# microcontrolador.net
KiCad netlist of a schematic drawn in Altium Designer
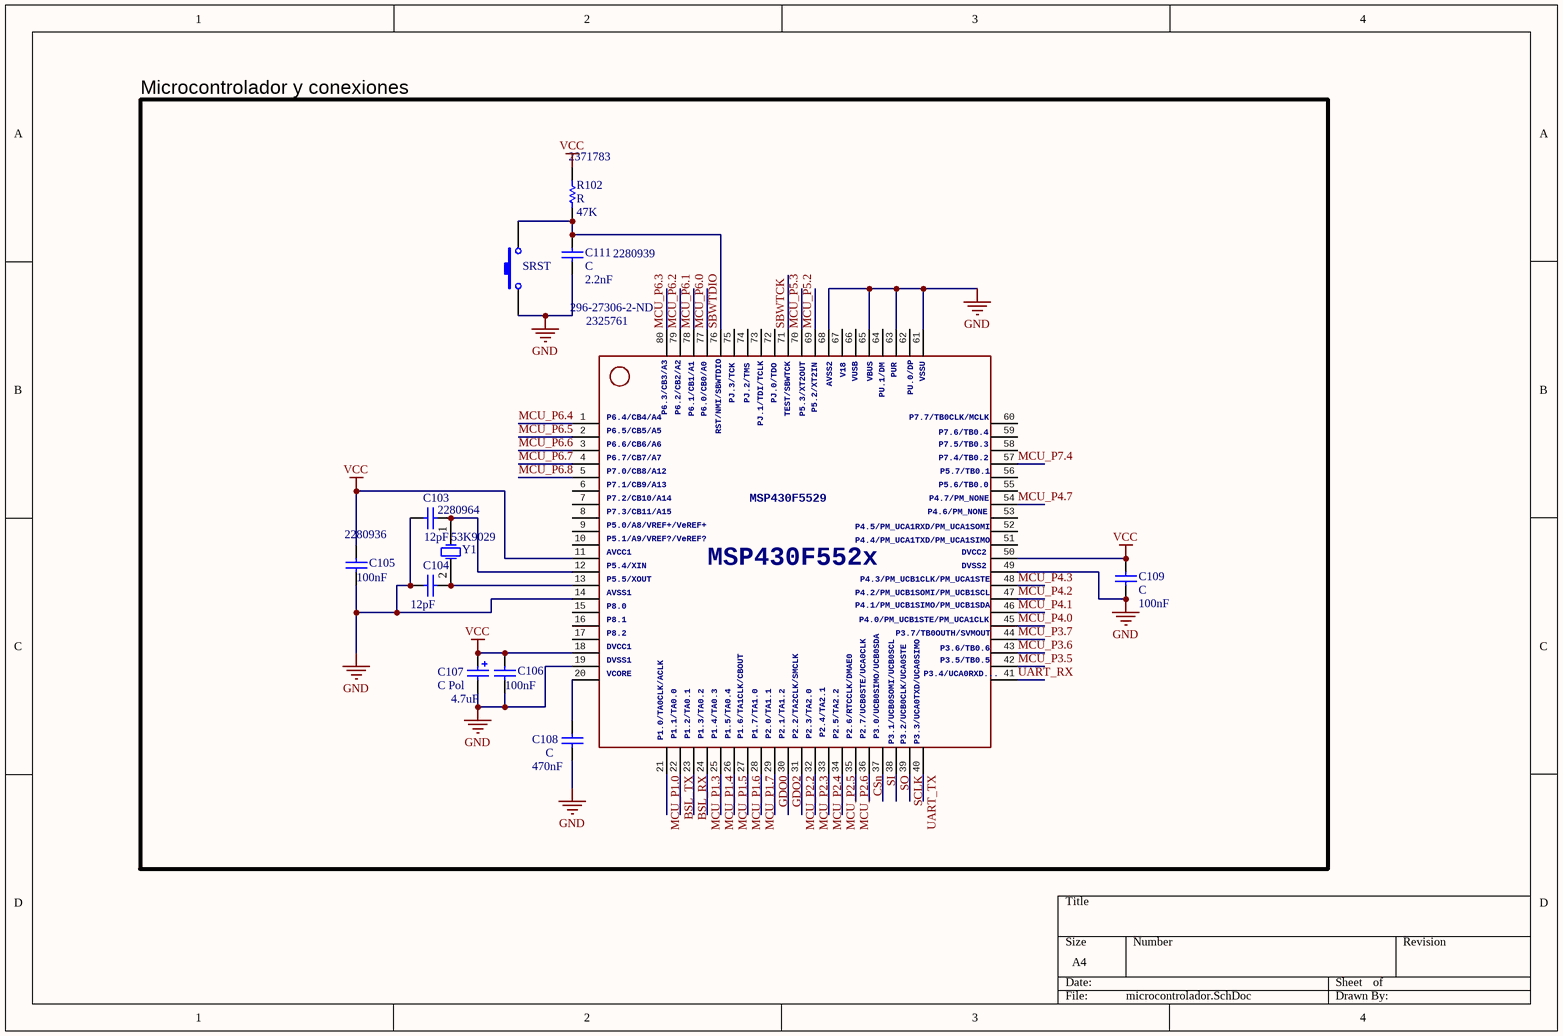
[diagram p0: microcontrolador.SchDoc]

(export (version "E")
  (design (tool "Eeschema 10.0.6"))
  (components
    (comp (ref "C103")
      (value "12pF")
      (footprint "0805 CAP")
      (description "Capacitor")
      (fields
        (field (name "MANUFACTURER") "Generic Components")
        (field (name "SUPPLIER PART NUMBER 1") "2280964")
        (field (name "Comment") "C")
        (field (name "PUBLISHER") "Altium Hobart Technology Centre")
      )
      (libsource (lib "LSI") (part "C"))
    )
    (comp (ref "C104")
      (value "12pF")
      (footprint "0805 CAP")
      (description "Capacitor")
      (fields
        (field (name "MANUFACTURER") "Generic Components")
        (field (name "Comment") "C")
        (field (name "PUBLISHER") "Altium Hobart Technology Centre")
      )
      (libsource (lib "LSI") (part "C"))
    )
    (comp (ref "C105")
      (value "100nF")
      (footprint "0805 CAP")
      (description "Capacitor")
      (fields
        (field (name "MANUFACTURER") "Generic Components")
        (field (name "SUPPLIER PART NUMBER 2") "2280936")
        (field (name "Comment") "C")
        (field (name "PUBLISHER") "Altium Hobart Technology Centre")
      )
      (libsource (lib "LSI") (part "C"))
    )
    (comp (ref "C106")
      (value "100nF")
      (footprint "0805 CAP")
      (description "Capacitor")
      (fields
        (field (name "MANUFACTURER") "Generic Components")
        (field (name "Comment") "C")
        (field (name "PUBLISHER") "Altium Hobart Technology Centre")
      )
      (libsource (lib "LSI") (part "C"))
    )
    (comp (ref "C107")
      (value "C Pol")
      (footprint "0805")
      (description "Polarized Capacitor (Surface Mount)")
      (fields
        (field (name "MANUFACTURER") "Generic Components")
        (field (name "ALTIUM_VALUE") "4.7uF")
        (field (name "PUBLISHER") "Altium Hobart Technology Centre")
      )
      (libsource (lib "LSI") (part "C Pol"))
    )
    (comp (ref "C108")
      (value "C")
      (footprint "0805 CAP")
      (description "Capacitor")
      (fields
        (field (name "MANUFACTURER") "Generic Components")
        (field (name "ALTIUM_VALUE") "470nF")
        (field (name "PUBLISHER") "Altium Hobart Technology Centre")
      )
      (libsource (lib "LSI") (part "C"))
    )
    (comp (ref "C109")
      (value "C")
      (footprint "0805 CAP")
      (description "Capacitor")
      (fields
        (field (name "MANUFACTURER") "Generic Components")
        (field (name "ALTIUM_VALUE") "100nF")
        (field (name "PUBLISHER") "Altium Hobart Technology Centre")
      )
      (libsource (lib "LSI") (part "C"))
    )
    (comp (ref "C111")
      (value "C")
      (footprint "0805 CAP")
      (description "Capacitor")
      (fields
        (field (name "MANUFACTURER") "Generic Components")
        (field (name "ALTIUM_VALUE") "2.2nF")
        (field (name "SUPPLIER PART NUMBER 1") "2280939")
        (field (name "PUBLISHER") "Altium Hobart Technology Centre")
      )
      (libsource (lib "LSI") (part "C"))
    )
    (comp (ref "MSP430F5529")
      (value "MSP430F5529IPNR")
      (footprint "TI-PN80_N")
      (fields
        (field (name "P6.3/CB3/A3") "P6.3/CB3/A3")
        (field (name "P6.2/CB2/A2") "P6.2/CB2/A2")
        (field (name "P6.1/CB1/A1") "P6.1/CB1/A1")
        (field (name "P6.0/CB0/A0") "P6.0/CB0/A0")
        (field (name "PJ.3/TCK") "PJ.3/TCK")
        (field (name "PJ.2/TMS") "PJ.2/TMS")
        (field (name "PJ.1/TDI/TCLK") "PJ.1/TDI/TCLK")
        (field (name "PJ.0/TDO") "PJ.0/TDO")
        (field (name "TEST/SBWTCK") "TEST/SBWTCK")
        (field (name "P5.3/XT2OUT") "P5.3/XT2OUT")
        (field (name "P5.2/XT2IN") "P5.2/XT2IN")
        (field (name "AVSS2") "AVSS2")
        (field (name "V18") "V18")
        (field (name "VUSB") "VUSB")
        (field (name "VBUS") "VBUS")
        (field (name "PU.1/DM") "PU.1/DM")
        (field (name "PUR") "PUR")
        (field (name "PU.0/DP") "PU.0/DP")
        (field (name "VSSU") "VSSU")
        (field (name "RST/NMI/SBWTDIO") "RST/NMI/SBWTDIO")
        (field (name "P7.7/TB0CLK/MCLK") "P7.7/TB0CLK/MCLK")
        (field (name "P7.6/TB0.4") "P7.6/TB0.4")
        (field (name "P7.5/TB0.3") "P7.5/TB0.3")
        (field (name "P7.4/TB0.2") "P7.4/TB0.2")
        (field (name "P5.7/TB0.1") "P5.7/TB0.1")
        (field (name "P5.6/TB0.0") "P5.6/TB0.0")
        (field (name "P4.7/PM_NONE") "P4.7/PM_NONE")
        (field (name "P4.5/PM_UCA1RXD/PM_UCA1SOMI") "P4.5/PM_UCA1RXD/PM_UCA1SOMI")
        (field (name "P4.4/PM_UCA1TXD/PM_UCA1SIMO") "P4.4/PM_UCA1TXD/PM_UCA1SIMO")
        (field (name "DVCC2") "DVCC2")
        (field (name "P4.3/PM_UCB1CLK/PM_UCA1STE") "P4.3/PM_UCB1CLK/PM_UCA1STE")
        (field (name "P4.2/PM_UCB1SOMI/PM_UCB1SCL") "P4.2/PM_UCB1SOMI/PM_UCB1SCL")
        (field (name "P4.1/PM_UCB1SIMO/PM_UCB1SDA") "P4.1/PM_UCB1SIMO/PM_UCB1SDA")
        (field (name "P4.0/PM_UCB1STE/PM_UCA1CLK") "P4.0/PM_UCB1STE/PM_UCA1CLK")
        (field (name "P3.7/TB0OUTH/SVMOUT") "P3.7/TB0OUTH/SVMOUT")
        (field (name "P3.6/TB0.6") "P3.6/TB0.6")
        (field (name "P4.6/PM_NONE") "P4.6/PM_NONE")
        (field (name "P3.5/TB0.5") "P3.5/TB0.5")
        (field (name "P3.4/UCA...") "P3.4/UCA0RXD...")
        (field (name "P1.0/TA0CLK/ACLK") "P1.0/TA0CLK/ACLK")
        (field (name "P1.1/TA0.0") "P1.1/TA0.0")
        (field (name "P1.2/TA0.1") "P1.2/TA0.1")
        (field (name "P1.3/TA0.2") "P1.3/TA0.2")
        (field (name "P1.4/TA0.3") "P1.4/TA0.3")
        (field (name "P1.5/TA0.4") "P1.5/TA0.4")
        (field (name "P1.6/TA1CLK/CBOUT") "P1.6/TA1CLK/CBOUT")
        (field (name "P1.7/TA1.0") "P1.7/TA1.0")
        (field (name "P2.0/TA1.1") "P2.0/TA1.1")
        (field (name "P2.1/TA1.2") "P2.1/TA1.2")
        (field (name "P2.2/TA2CLK/SMCLK") "P2.2/TA2CLK/SMCLK")
        (field (name "P2.4/TA2.1") "P2.4/TA2.1")
        (field (name "P2.5/TA2.2") "P2.5/TA2.2")
        (field (name "P2.6/RTCCLK/DMAE0") "P2.6/RTCCLK/DMAE0")
        (field (name "P2.7/UCB0STE/UCA0CLK") "P2.7/UCB0STE/UCA0CLK")
        (field (name "P3.0/UCB0SIMO/UCB0SDA") "P3.0/UCB0SIMO/UCB0SDA")
        (field (name "P3.1/UCB0SOMI/UCB0SCL") "P3.1/UCB0SOMI/UCB0SCL")
        (field (name "P3.2/UCB0CLK/UCA0STE") "P3.2/UCB0CLK/UCA0STE")
        (field (name "P3.3/UCA0TXD/UCA0SIMO") "P3.3/UCA0TXD/UCA0SIMO")
        (field (name "P6.4/CB4/A4") "P6.4/CB4/A4")
        (field (name "P6.5/CB5/A5") "P6.5/CB5/A5")
        (field (name "P6.6/CB6/A6") "P6.6/CB6/A6")
        (field (name "P6.7/CB7/A7") "P6.7/CB7/A7")
        (field (name "P7.0/CB8/A12") "P7.0/CB8/A12")
        (field (name "P7.1/CB9/A13") "P7.1/CB9/A13")
        (field (name "P7.2/CB10/A14") "P7.2/CB10/A14")
        (field (name "P7.3/CB11/A15") "P7.3/CB11/A15")
        (field (name "P5.0/A8/VREF+/VEREF+") "P5.0/A8/VREF+/VeREF+")
        (field (name "P5.1/A9/VREF?/VEREF?") "P5.1/A9/VREF?/VeREF?")
        (field (name "AVCC1") "AVCC1")
        (field (name "P5.4/XIN") "P5.4/XIN")
        (field (name "P5.5/XOUT") "P5.5/XOUT")
        (field (name "AVSS1") "AVSS1")
        (field (name "P8.0") "P8.0")
        (field (name "P8.1") "P8.1")
        (field (name "P8.2") "P8.2")
        (field (name "DVCC1") "DVCC1")
        (field (name "DVSS1") "DVSS1")
        (field (name "VCORE") "VCORE")
        (field (name "MSP430F552X") "MSP430F552x")
        (field (name "DVSS2") "DVSS2")
        (field (name "P2.3/TA2.0") "P2.3/TA2.0")
        (field (name "SUPPLIER PART NUMBER 1") "2325761")
        (field (name "SUPPLIER PART NUMBER 2") "296-27306-2-ND")
      )
      (libsource (lib "LSI") (part "F552X---PN80"))
    )
    (comp (ref "R102")
      (value "R")
      (footprint "0805 RES")
      (description "Resistor")
      (fields
        (field (name "MANUFACTURER") "Generic Components")
        (field (name "ALTIUM_VALUE") "47K")
        (field (name "SUPPLIER PART NUMBER 1") "2371783")
        (field (name "PUBLISHER") "Altium Hobart Technology Centre")
      )
      (libsource (lib "LSI") (part "R"))
    )
    (comp (ref "SRST")
      (value "Pulsador")
      (footprint "B3U-1000P")
      (description "Switch")
      (fields (field (name "MANUFACTURER") "Generic Components"))
      (libsource (lib "LSI") (part "Pulsador_1"))
    )
    (comp (ref "Y1")
      (value "XTAL_CFPX-157_32.768K_SMD")
      (footprint "R38")
      (description "Crystal Oscillator")
      (fields
        (field (name "MANUFACTURER") "Generic Components")
        (field (name "SUPPLIER PART NUMBER 1") "53K9029")
        (field (name "PUBLISHER") "Altium Hobart Technology Centre")
      )
      (libsource (lib "LSI") (part "XTAL_CFPX-157_32.768K_SMD"))
    )
  )
  (nets
    (net (code "1") (name "/BSL_RX") (class "Default")
      (node (ref "MSP430F5529") (pin "23") (pinfunction "23_23") (pintype "passive"))
    )
    (net (code "2") (name "/BSL_TX") (class "Default")
      (node (ref "MSP430F5529") (pin "22") (pinfunction "22_22") (pintype "passive"))
    )
    (net (code "3") (name "/CSn") (class "Default")
      (node (ref "MSP430F5529") (pin "36") (pinfunction "36_36") (pintype "passive"))
    )
    (net (code "4") (name "/GDO0") (class "Default")
      (node (ref "MSP430F5529") (pin "29") (pinfunction "29_29") (pintype "passive"))
    )
    (net (code "5") (name "/GDO2") (class "Default")
      (node (ref "MSP430F5529") (pin "30") (pinfunction "30_30") (pintype "passive"))
    )
    (net (code "6") (name "/MCU_P1.0") (class "Default")
      (node (ref "MSP430F5529") (pin "21") (pinfunction "21_21") (pintype "passive"))
    )
    (net (code "7") (name "/MCU_P1.3") (class "Default")
      (node (ref "MSP430F5529") (pin "24") (pinfunction "24_24") (pintype "passive"))
    )
    (net (code "8") (name "/MCU_P1.4") (class "Default")
      (node (ref "MSP430F5529") (pin "25") (pinfunction "25_25") (pintype "passive"))
    )
    (net (code "9") (name "/MCU_P1.5") (class "Default")
      (node (ref "MSP430F5529") (pin "26") (pinfunction "26_26") (pintype "passive"))
    )
    (net (code "10") (name "/MCU_P1.6") (class "Default")
      (node (ref "MSP430F5529") (pin "27") (pinfunction "27_27") (pintype "passive"))
    )
    (net (code "11") (name "/MCU_P1.7") (class "Default")
      (node (ref "MSP430F5529") (pin "28") (pinfunction "28_28") (pintype "passive"))
    )
    (net (code "12") (name "/MCU_P2.2") (class "Default")
      (node (ref "MSP430F5529") (pin "31") (pinfunction "31_31") (pintype "passive"))
    )
    (net (code "13") (name "/MCU_P2.3") (class "Default")
      (node (ref "MSP430F5529") (pin "32") (pinfunction "32_32") (pintype "passive"))
    )
    (net (code "14") (name "/MCU_P2.4") (class "Default")
      (node (ref "MSP430F5529") (pin "33") (pinfunction "33_33") (pintype "passive"))
    )
    (net (code "15") (name "/MCU_P2.5") (class "Default")
      (node (ref "MSP430F5529") (pin "34") (pinfunction "34_34") (pintype "passive"))
    )
    (net (code "16") (name "/MCU_P2.6") (class "Default")
      (node (ref "MSP430F5529") (pin "35") (pinfunction "35_35") (pintype "passive"))
    )
    (net (code "17") (name "/MCU_P3.5") (class "Default")
      (node (ref "MSP430F5529") (pin "42") (pinfunction "42_42") (pintype "passive"))
    )
    (net (code "18") (name "/MCU_P3.6") (class "Default")
      (node (ref "MSP430F5529") (pin "43") (pinfunction "43_43") (pintype "passive"))
    )
    (net (code "19") (name "/MCU_P3.7") (class "Default")
      (node (ref "MSP430F5529") (pin "44") (pinfunction "44_44") (pintype "passive"))
    )
    (net (code "20") (name "/MCU_P4.0") (class "Default")
      (node (ref "MSP430F5529") (pin "45") (pinfunction "45_45") (pintype "passive"))
    )
    (net (code "21") (name "/MCU_P4.1") (class "Default")
      (node (ref "MSP430F5529") (pin "46") (pinfunction "46_46") (pintype "passive"))
    )
    (net (code "22") (name "/MCU_P4.2") (class "Default")
      (node (ref "MSP430F5529") (pin "47") (pinfunction "47_47") (pintype "passive"))
    )
    (net (code "23") (name "/MCU_P4.3") (class "Default")
      (node (ref "MSP430F5529") (pin "48") (pinfunction "48_48") (pintype "passive"))
    )
    (net (code "24") (name "/MCU_P4.7") (class "Default")
      (node (ref "MSP430F5529") (pin "54") (pinfunction "54_54") (pintype "passive"))
    )
    (net (code "25") (name "/MCU_P5.2") (class "Default")
      (node (ref "MSP430F5529") (pin "69") (pinfunction "69_69") (pintype "passive"))
    )
    (net (code "26") (name "/MCU_P5.3") (class "Default")
      (node (ref "MSP430F5529") (pin "70") (pinfunction "70_70") (pintype "passive"))
    )
    (net (code "27") (name "/MCU_P6.0") (class "Default")
      (node (ref "MSP430F5529") (pin "77") (pinfunction "77_77") (pintype "passive"))
    )
    (net (code "28") (name "/MCU_P6.1") (class "Default")
      (node (ref "MSP430F5529") (pin "78") (pinfunction "78_78") (pintype "passive"))
    )
    (net (code "29") (name "/MCU_P6.2") (class "Default")
      (node (ref "MSP430F5529") (pin "79") (pinfunction "79_79") (pintype "passive"))
    )
    (net (code "30") (name "/MCU_P6.3") (class "Default")
      (node (ref "MSP430F5529") (pin "80") (pinfunction "80_80") (pintype "passive"))
    )
    (net (code "31") (name "/MCU_P6.4") (class "Default")
      (node (ref "MSP430F5529") (pin "1") (pinfunction "1_1") (pintype "passive"))
    )
    (net (code "32") (name "/MCU_P6.5") (class "Default")
      (node (ref "MSP430F5529") (pin "2") (pinfunction "2_2") (pintype "passive"))
    )
    (net (code "33") (name "/MCU_P6.6") (class "Default")
      (node (ref "MSP430F5529") (pin "3") (pinfunction "3_3") (pintype "passive"))
    )
    (net (code "34") (name "/MCU_P6.7") (class "Default")
      (node (ref "MSP430F5529") (pin "4") (pinfunction "4_4") (pintype "passive"))
    )
    (net (code "35") (name "/MCU_P6.8") (class "Default")
      (node (ref "MSP430F5529") (pin "5") (pinfunction "5_5") (pintype "passive"))
    )
    (net (code "36") (name "/MCU_P7.4") (class "Default")
      (node (ref "MSP430F5529") (pin "57") (pinfunction "57_57") (pintype "passive"))
    )
    (net (code "37") (name "/SBWTCK") (class "Default")
      (node (ref "MSP430F5529") (pin "71") (pinfunction "71_71") (pintype "passive"))
    )
    (net (code "38") (name "/SBWTDIO") (class "Default")
      (node (ref "C111") (pin "2") (pinfunction "2_2") (pintype "passive"))
      (node (ref "MSP430F5529") (pin "76") (pinfunction "76_76") (pintype "passive"))
      (node (ref "R102") (pin "1") (pinfunction "1_1") (pintype "passive"))
      (node (ref "SRST") (pin "2") (pinfunction "2_2") (pintype "passive"))
    )
    (net (code "39") (name "/SCLK") (class "Default")
      (node (ref "MSP430F5529") (pin "39") (pinfunction "39_39") (pintype "passive"))
    )
    (net (code "40") (name "/SI") (class "Default")
      (node (ref "MSP430F5529") (pin "37") (pinfunction "37_37") (pintype "passive"))
    )
    (net (code "41") (name "/SO") (class "Default")
      (node (ref "MSP430F5529") (pin "38") (pinfunction "38_38") (pintype "passive"))
    )
    (net (code "42") (name "/UART_RX") (class "Default")
      (node (ref "MSP430F5529") (pin "41") (pinfunction "41_41") (pintype "passive"))
    )
    (net (code "43") (name "/UART_TX") (class "Default")
      (node (ref "MSP430F5529") (pin "40") (pinfunction "40_40") (pintype "passive"))
    )
    (net (code "44") (name "GND") (class "Default")
      (node (ref "C103") (pin "1") (pinfunction "1_1") (pintype "passive"))
      (node (ref "C104") (pin "1") (pinfunction "1_1") (pintype "passive"))
      (node (ref "C105") (pin "2") (pinfunction "2_2") (pintype "passive"))
      (node (ref "C106") (pin "2") (pinfunction "2_2") (pintype "passive"))
      (node (ref "C107") (pin "2") (pinfunction "2_2") (pintype "passive"))
      (node (ref "C108") (pin "1") (pinfunction "1_1") (pintype "passive"))
      (node (ref "C109") (pin "1") (pinfunction "1_1") (pintype "passive"))
      (node (ref "C111") (pin "1") (pinfunction "1_1") (pintype "passive"))
      (node (ref "MSP430F5529") (pin "14") (pinfunction "14_14") (pintype "power_in"))
      (node (ref "MSP430F5529") (pin "19") (pinfunction "19_19") (pintype "power_in"))
      (node (ref "MSP430F5529") (pin "49") (pinfunction "49_49") (pintype "power_in"))
      (node (ref "MSP430F5529") (pin "61") (pinfunction "61_61") (pintype "power_in"))
      (node (ref "MSP430F5529") (pin "63") (pinfunction "63_63") (pintype "passive"))
      (node (ref "MSP430F5529") (pin "65") (pinfunction "65_65") (pintype "power_in"))
      (node (ref "MSP430F5529") (pin "68") (pinfunction "68_68") (pintype "power_in"))
      (node (ref "SRST") (pin "1") (pinfunction "1_1") (pintype "passive"))
    )
    (net (code "45") (name "Net-(C108-Pad2)") (class "Default")
      (node (ref "C108") (pin "2") (pinfunction "2_2") (pintype "passive"))
      (node (ref "MSP430F5529") (pin "20") (pinfunction "20_20") (pintype "power_in"))
    )
    (net (code "46") (name "Net-(Y1-OSC1)") (class "Default")
      (node (ref "C103") (pin "2") (pinfunction "2_2") (pintype "passive"))
      (node (ref "MSP430F5529") (pin "12") (pinfunction "12_12") (pintype "passive"))
      (node (ref "Y1") (pin "1") (pinfunction "OSC1_1") (pintype "passive"))
    )
    (net (code "47") (name "Net-(Y1-OSC2)") (class "Default")
      (node (ref "C104") (pin "2") (pinfunction "2_2") (pintype "passive"))
      (node (ref "MSP430F5529") (pin "13") (pinfunction "13_13") (pintype "passive"))
      (node (ref "Y1") (pin "2") (pinfunction "OSC2_2") (pintype "passive"))
    )
    (net (code "48") (name "VCC") (class "Default")
      (node (ref "C105") (pin "1") (pinfunction "1_1") (pintype "passive"))
      (node (ref "C106") (pin "1") (pinfunction "1_1") (pintype "passive"))
      (node (ref "C107") (pin "1") (pinfunction "1_1") (pintype "passive"))
      (node (ref "C109") (pin "2") (pinfunction "2_2") (pintype "passive"))
      (node (ref "MSP430F5529") (pin "11") (pinfunction "11_11") (pintype "power_in"))
      (node (ref "MSP430F5529") (pin "18") (pinfunction "18_18") (pintype "power_in"))
      (node (ref "MSP430F5529") (pin "50") (pinfunction "50_50") (pintype "power_in"))
      (node (ref "R102") (pin "2") (pinfunction "2_2") (pintype "passive"))
    )
    (net (code "49") (name "unconnected-(MSP430F5529-Pad6)") (class "Default")
      (node (ref "MSP430F5529") (pin "6") (pinfunction "6_6") (pintype "passive"))
    )
    (net (code "50") (name "unconnected-(MSP430F5529-Pad7)") (class "Default")
      (node (ref "MSP430F5529") (pin "7") (pinfunction "7_7") (pintype "passive"))
    )
    (net (code "51") (name "unconnected-(MSP430F5529-Pad8)") (class "Default")
      (node (ref "MSP430F5529") (pin "8") (pinfunction "8_8") (pintype "passive"))
    )
    (net (code "52") (name "unconnected-(MSP430F5529-Pad9)") (class "Default")
      (node (ref "MSP430F5529") (pin "9") (pinfunction "9_9") (pintype "passive"))
    )
    (net (code "53") (name "unconnected-(MSP430F5529-Pad10)") (class "Default")
      (node (ref "MSP430F5529") (pin "10") (pinfunction "10_10") (pintype "passive"))
    )
    (net (code "54") (name "unconnected-(MSP430F5529-Pad15)") (class "Default")
      (node (ref "MSP430F5529") (pin "15") (pinfunction "15_15") (pintype "passive"))
    )
    (net (code "55") (name "unconnected-(MSP430F5529-Pad16)") (class "Default")
      (node (ref "MSP430F5529") (pin "16") (pinfunction "16_16") (pintype "passive"))
    )
    (net (code "56") (name "unconnected-(MSP430F5529-Pad17)") (class "Default")
      (node (ref "MSP430F5529") (pin "17") (pinfunction "17_17") (pintype "passive"))
    )
    (net (code "57") (name "unconnected-(MSP430F5529-Pad51)") (class "Default")
      (node (ref "MSP430F5529") (pin "51") (pinfunction "51_51") (pintype "passive"))
    )
    (net (code "58") (name "unconnected-(MSP430F5529-Pad52)") (class "Default")
      (node (ref "MSP430F5529") (pin "52") (pinfunction "52_52") (pintype "passive"))
    )
    (net (code "59") (name "unconnected-(MSP430F5529-Pad53)") (class "Default")
      (node (ref "MSP430F5529") (pin "53") (pinfunction "53_53") (pintype "passive"))
    )
    (net (code "60") (name "unconnected-(MSP430F5529-Pad55)") (class "Default")
      (node (ref "MSP430F5529") (pin "55") (pinfunction "55_55") (pintype "passive"))
    )
    (net (code "61") (name "unconnected-(MSP430F5529-Pad56)") (class "Default")
      (node (ref "MSP430F5529") (pin "56") (pinfunction "56_56") (pintype "passive"))
    )
    (net (code "62") (name "unconnected-(MSP430F5529-Pad58)") (class "Default")
      (node (ref "MSP430F5529") (pin "58") (pinfunction "58_58") (pintype "passive"))
    )
    (net (code "63") (name "unconnected-(MSP430F5529-Pad59)") (class "Default")
      (node (ref "MSP430F5529") (pin "59") (pinfunction "59_59") (pintype "passive"))
    )
    (net (code "64") (name "unconnected-(MSP430F5529-Pad60)") (class "Default")
      (node (ref "MSP430F5529") (pin "60") (pinfunction "60_60") (pintype "passive"))
    )
    (net (code "65") (name "unconnected-(MSP430F5529-Pad62)") (class "Default")
      (node (ref "MSP430F5529") (pin "62") (pinfunction "62_62") (pintype "passive"))
    )
    (net (code "66") (name "unconnected-(MSP430F5529-Pad64)") (class "Default")
      (node (ref "MSP430F5529") (pin "64") (pinfunction "64_64") (pintype "passive"))
    )
    (net (code "67") (name "unconnected-(MSP430F5529-Pad66)") (class "Default")
      (node (ref "MSP430F5529") (pin "66") (pinfunction "66_66") (pintype "power_in"))
    )
    (net (code "68") (name "unconnected-(MSP430F5529-Pad67)") (class "Default")
      (node (ref "MSP430F5529") (pin "67") (pinfunction "67_67") (pintype "power_in"))
    )
    (net (code "69") (name "unconnected-(MSP430F5529-Pad72)") (class "Default")
      (node (ref "MSP430F5529") (pin "72") (pinfunction "72_72") (pintype "passive"))
    )
    (net (code "70") (name "unconnected-(MSP430F5529-Pad73)") (class "Default")
      (node (ref "MSP430F5529") (pin "73") (pinfunction "73_73") (pintype "passive"))
    )
    (net (code "71") (name "unconnected-(MSP430F5529-Pad74)") (class "Default")
      (node (ref "MSP430F5529") (pin "74") (pinfunction "74_74") (pintype "passive"))
    )
    (net (code "72") (name "unconnected-(MSP430F5529-Pad75)") (class "Default")
      (node (ref "MSP430F5529") (pin "75") (pinfunction "75_75") (pintype "passive"))
    )
  )
)
